# 5V_POWER_SUPPLY.net
KiCad netlist of a schematic drawn in EAGLE
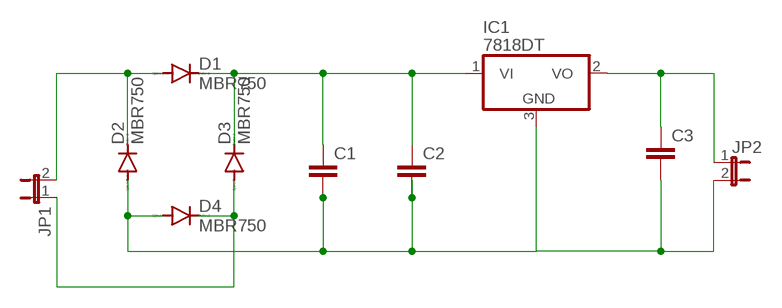
[diagram p0: schematic, sheet 1]

(export (version "E")
  (design (tool "Eeschema 10.0.6"))
  (components
    (comp (ref "C1")
      (value "C22/6")
      (footprint "eagle-import:C22.5B6")
      (libsource (lib "eagle-import") (part "C22/6"))
    )
    (comp (ref "C2")
      (value "C22/6")
      (footprint "eagle-import:C22.5B6")
      (libsource (lib "eagle-import") (part "C22/6"))
    )
    (comp (ref "C3")
      (value "C22/6")
      (footprint "eagle-import:C22.5B6")
      (libsource (lib "eagle-import") (part "C22/6"))
    )
    (comp (ref "D1")
      (value "MBR750")
      (footprint "eagle-import:TO220AC")
      (libsource (lib "eagle-import") (part "MBR750"))
    )
    (comp (ref "D2")
      (value "MBR750")
      (footprint "eagle-import:TO220AC")
      (libsource (lib "eagle-import") (part "MBR750"))
    )
    (comp (ref "D3")
      (value "MBR750")
      (footprint "eagle-import:TO220AC")
      (libsource (lib "eagle-import") (part "MBR750"))
    )
    (comp (ref "D4")
      (value "MBR750")
      (footprint "eagle-import:TO220AC")
      (libsource (lib "eagle-import") (part "MBR750"))
    )
    (comp (ref "IC1")
      (value "7818DT")
      (footprint "eagle-import:TO252")
      (libsource (lib "eagle-import") (part "78DT18"))
    )
    (comp (ref "JP1")
      (value "JP1E")
      (footprint "eagle-import:JP1")
      (libsource (lib "eagle-import") (part "JP1E"))
    )
    (comp (ref "JP2")
      (value "JP1E")
      (footprint "eagle-import:JP1")
      (libsource (lib "eagle-import") (part "JP1E"))
    )
  )
  (nets
    (net (code "1") (name "Net-(D1-PadA)") (class "Default")
      (node (ref "D1") (pin "A") (pinfunction "A_A") (pintype "passive"))
      (node (ref "D2") (pin "C") (pinfunction "C_C") (pintype "passive"))
      (node (ref "JP1") (pin "2") (pinfunction "2_2") (pintype "passive"))
    )
    (net (code "2") (name "Net-(D3-PadA)") (class "Default")
      (node (ref "D3") (pin "A") (pinfunction "A_A") (pintype "passive"))
      (node (ref "D4") (pin "C") (pinfunction "C_C") (pintype "passive"))
      (node (ref "JP1") (pin "1") (pinfunction "1_1") (pintype "passive"))
    )
    (net (code "3") (name "Net-(IC1-GND)") (class "Default")
      (node (ref "C1") (pin "2") (pinfunction "2_2") (pintype "passive"))
      (node (ref "C2") (pin "2") (pinfunction "2_2") (pintype "passive"))
      (node (ref "C3") (pin "2") (pinfunction "2_2") (pintype "passive"))
      (node (ref "D2") (pin "A") (pinfunction "A_A") (pintype "passive"))
      (node (ref "D4") (pin "A") (pinfunction "A_A") (pintype "passive"))
      (node (ref "IC1") (pin "3") (pinfunction "GND_3") (pintype "passive"))
      (node (ref "JP2") (pin "2") (pinfunction "2_2") (pintype "passive"))
    )
    (net (code "4") (name "Net-(IC1-VI)") (class "Default")
      (node (ref "C1") (pin "1") (pinfunction "1_1") (pintype "passive"))
      (node (ref "C2") (pin "1") (pinfunction "1_1") (pintype "passive"))
      (node (ref "D1") (pin "C") (pinfunction "C_C") (pintype "passive"))
      (node (ref "D3") (pin "C") (pinfunction "C_C") (pintype "passive"))
      (node (ref "IC1") (pin "1") (pinfunction "VI_1") (pintype "input"))
    )
    (net (code "5") (name "Net-(IC1-VO)") (class "Default")
      (node (ref "C3") (pin "1") (pinfunction "1_1") (pintype "passive"))
      (node (ref "IC1") (pin "2") (pinfunction "VO_2") (pintype "passive"))
      (node (ref "JP2") (pin "1") (pinfunction "1_1") (pintype "passive"))
    )
  )
)
